# Orange_Board.net
KiCad netlist of a schematic drawn in EAGLE
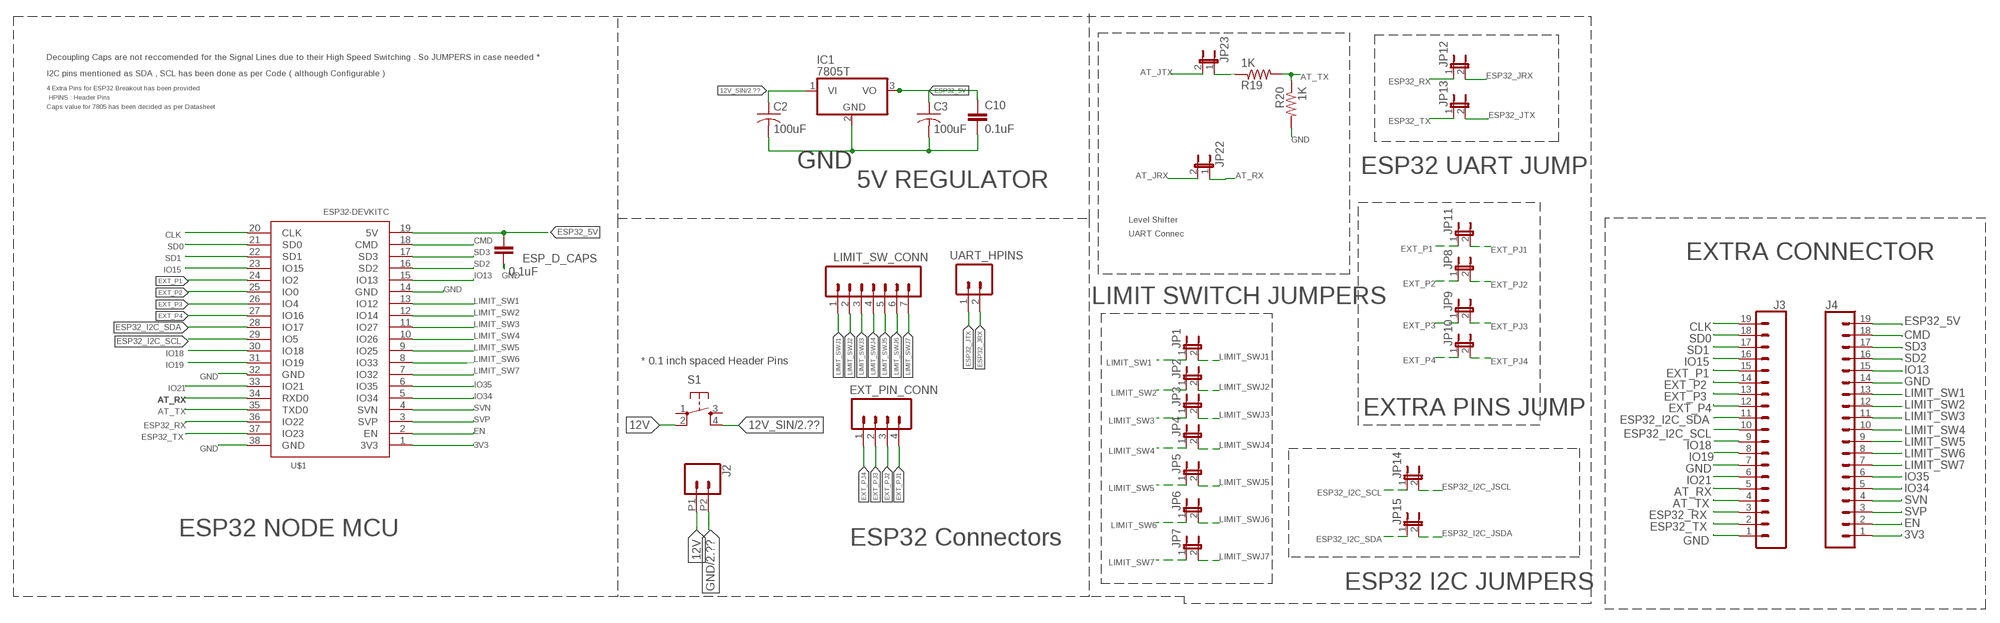
[diagram p0: schematic, sheet 1]
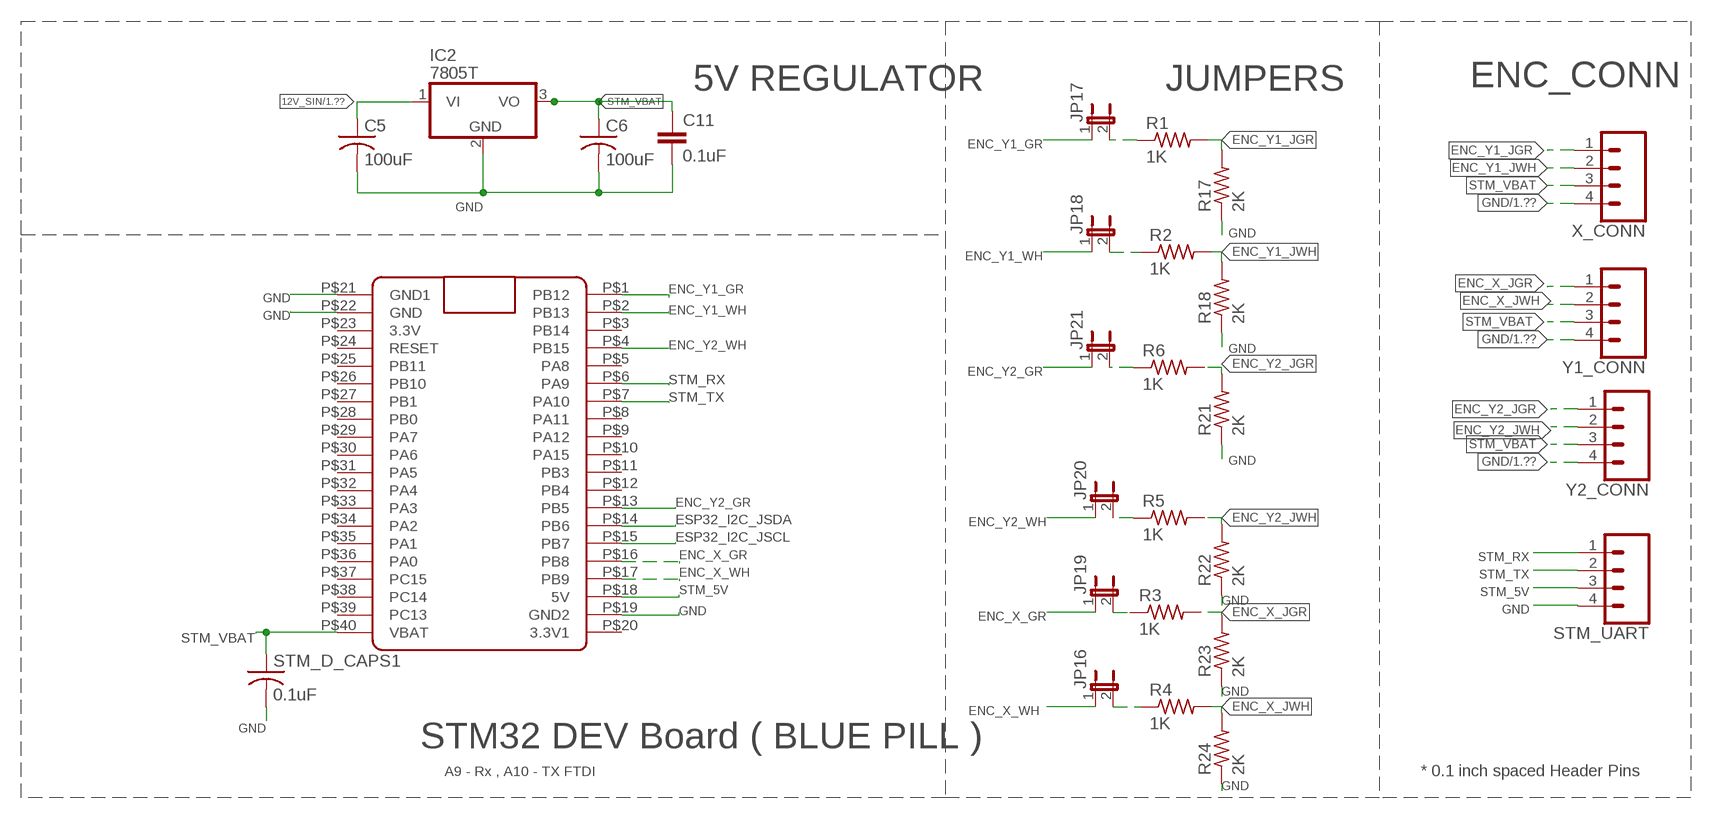
[diagram p1: schematic, sheet 2]
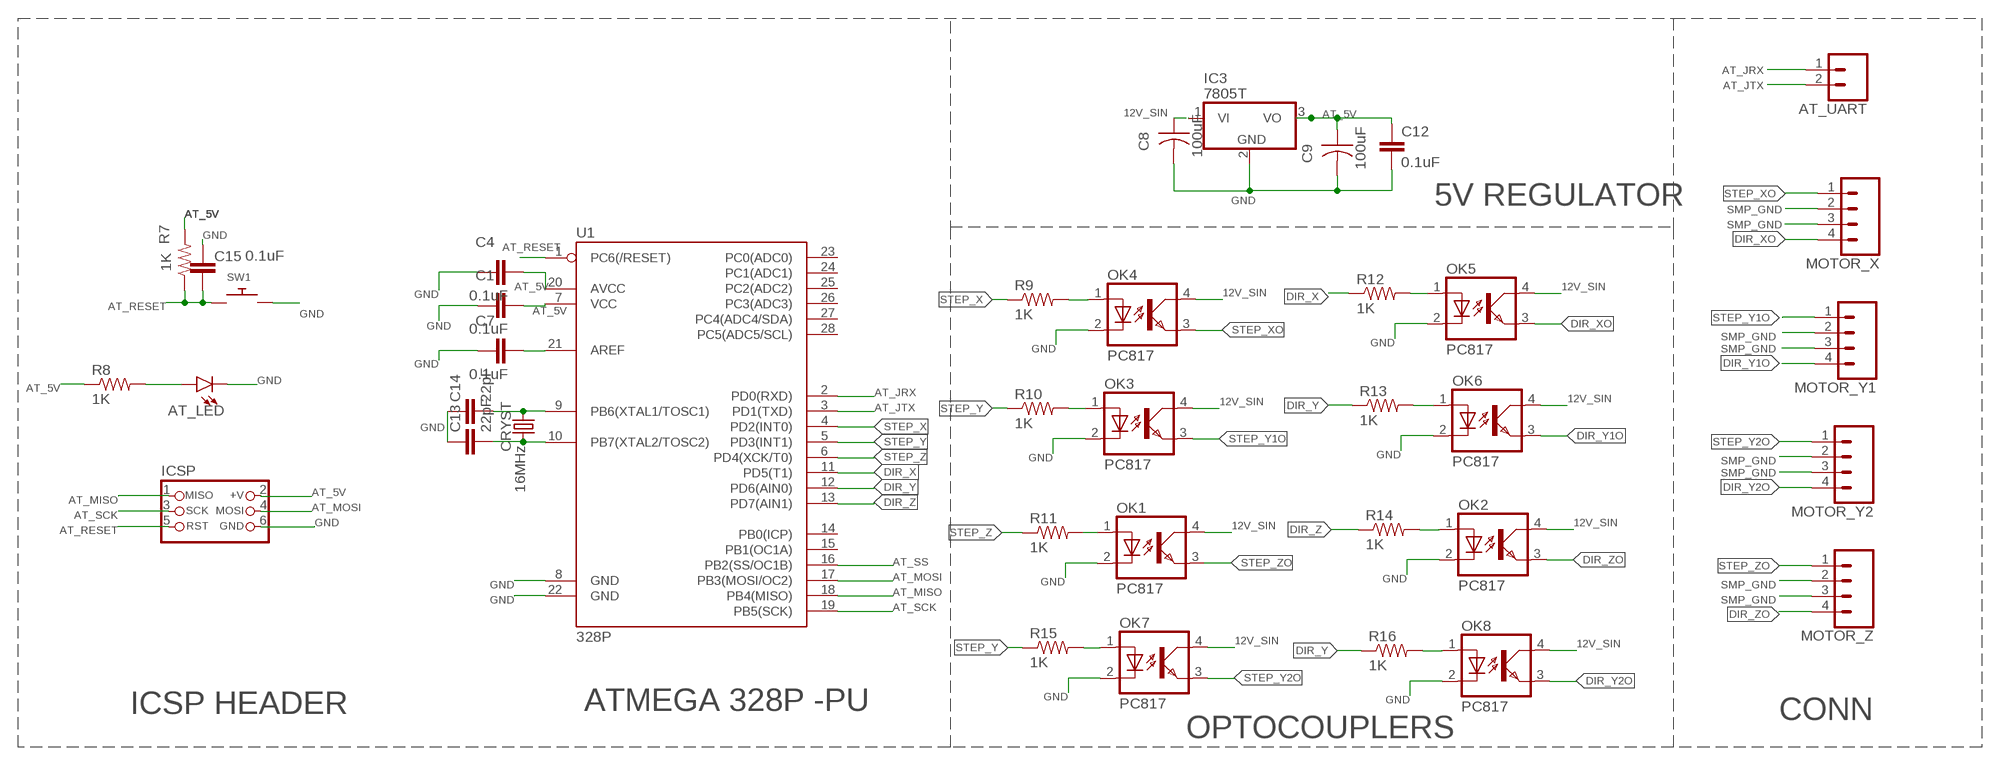
[diagram p2: schematic, sheet 3]

(export (version "E")
  (design (tool "Eeschema 10.0.6"))
  (components
    (comp (ref "C5")
      (value "100uF")
      (footprint "eagle-import:C025-024X044")
      (libsource (lib "eagle-import") (part "C-US025-024X044"))
    )
    (comp (ref "C6")
      (value "100uF")
      (footprint "eagle-import:C025-024X044")
      (libsource (lib "eagle-import") (part "C-US025-024X044"))
    )
    (comp (ref "C11")
      (value "0.1uF")
      (footprint "eagle-import:CAP-PTH-SMALL-KIT")
      (libsource (lib "eagle-import") (part "0.1UF-KIT-EZ-50V-20%"))
    )
    (comp (ref "IC2")
      (value "7805T")
      (footprint "eagle-import:TO220H")
      (libsource (lib "eagle-import") (part "78T05"))
    )
    (comp (ref "JP16")
      (value "JUMPER-2PTH")
      (footprint "eagle-import:1X02")
      (libsource (lib "eagle-import") (part "JUMPER-2PTH"))
    )
    (comp (ref "JP17")
      (value "JUMPER-2PTH")
      (footprint "eagle-import:1X02")
      (libsource (lib "eagle-import") (part "JUMPER-2PTH"))
    )
    (comp (ref "JP18")
      (value "JUMPER-2PTH")
      (footprint "eagle-import:1X02")
      (libsource (lib "eagle-import") (part "JUMPER-2PTH"))
    )
    (comp (ref "JP19")
      (value "JUMPER-2PTH")
      (footprint "eagle-import:1X02")
      (libsource (lib "eagle-import") (part "JUMPER-2PTH"))
    )
    (comp (ref "JP20")
      (value "JUMPER-2PTH")
      (footprint "eagle-import:1X02")
      (libsource (lib "eagle-import") (part "JUMPER-2PTH"))
    )
    (comp (ref "JP21")
      (value "JUMPER-2PTH")
      (footprint "eagle-import:1X02")
      (libsource (lib "eagle-import") (part "JUMPER-2PTH"))
    )
    (comp (ref "R1")
      (value "1K")
      (footprint "eagle-import:0204_5")
      (libsource (lib "eagle-import") (part "R-US_0204/5"))
    )
    (comp (ref "R2")
      (value "1K")
      (footprint "eagle-import:0204_5")
      (libsource (lib "eagle-import") (part "R-US_0204/5"))
    )
    (comp (ref "R3")
      (value "1K")
      (footprint "eagle-import:0204_5")
      (libsource (lib "eagle-import") (part "R-US_0204/5"))
    )
    (comp (ref "R4")
      (value "1K")
      (footprint "eagle-import:0204_5")
      (libsource (lib "eagle-import") (part "R-US_0204/5"))
    )
    (comp (ref "R5")
      (value "1K")
      (footprint "eagle-import:0204_5")
      (libsource (lib "eagle-import") (part "R-US_0204/5"))
    )
    (comp (ref "R6")
      (value "1K")
      (footprint "eagle-import:0204_5")
      (libsource (lib "eagle-import") (part "R-US_0204/5"))
    )
    (comp (ref "R17")
      (value "2K")
      (footprint "eagle-import:0204_5")
      (libsource (lib "eagle-import") (part "R-US_0204/5"))
    )
    (comp (ref "R18")
      (value "2K")
      (footprint "eagle-import:0204_5")
      (libsource (lib "eagle-import") (part "R-US_0204/5"))
    )
    (comp (ref "R21")
      (value "2K")
      (footprint "eagle-import:0204_5")
      (libsource (lib "eagle-import") (part "R-US_0204/5"))
    )
    (comp (ref "R22")
      (value "2K")
      (footprint "eagle-import:0204_5")
      (libsource (lib "eagle-import") (part "R-US_0204/5"))
    )
    (comp (ref "R23")
      (value "2K")
      (footprint "eagle-import:0204_5")
      (libsource (lib "eagle-import") (part "R-US_0204/5"))
    )
    (comp (ref "R24")
      (value "2K")
      (footprint "eagle-import:0204_5")
      (libsource (lib "eagle-import") (part "R-US_0204/5"))
    )
    (comp (ref "STM_D_CAPS1")
      (value "0.1uF")
      (footprint "eagle-import:C025-024X044")
      (libsource (lib "eagle-import") (part "C-US025-024X044"))
    )
    (comp (ref "STM_UART")
      (value "CONN_04")
      (footprint "eagle-import:1X04")
      (libsource (lib "eagle-import") (part "CONN_04"))
    )
    (comp (ref "U$2")
      (value "BLUE_PILLADVANCED")
      (footprint "eagle-import:BLUE_PILL_ADV")
      (libsource (lib "eagle-import") (part "BLUE_PILLADVANCED"))
    )
    (comp (ref "X_CONN")
      (value "CONN_04")
      (footprint "eagle-import:1X04")
      (libsource (lib "eagle-import") (part "CONN_04"))
    )
    (comp (ref "Y1_CONN")
      (value "CONN_04")
      (footprint "eagle-import:1X04")
      (libsource (lib "eagle-import") (part "CONN_04"))
    )
    (comp (ref "Y2_CONN")
      (value "CONN_04")
      (footprint "eagle-import:1X04")
      (libsource (lib "eagle-import") (part "CONN_04"))
    )
    (comp (ref "AT_LED")
      (value "LED-3MM-NO_SILK")
      (footprint "eagle-import:LED_3MM-NS")
      (libsource (lib "eagle-import") (part "LED-3MM-NO_SILK"))
    )
    (comp (ref "AT_UART")
      (value "CONN_02")
      (footprint "eagle-import:1X02")
      (libsource (lib "eagle-import") (part "CONN_02"))
    )
    (comp (ref "C1")
      (value "0.1uF")
      (footprint "eagle-import:CAP-PTH-SMALL-KIT")
      (libsource (lib "eagle-import") (part "0.1UF-KIT-EZ-50V-20%"))
    )
    (comp (ref "C4")
      (value "0.1uF")
      (footprint "eagle-import:CAP-PTH-SMALL-KIT")
      (libsource (lib "eagle-import") (part "0.1UF-KIT-EZ-50V-20%"))
    )
    (comp (ref "C7")
      (value "0.1uF")
      (footprint "eagle-import:CAP-PTH-SMALL-KIT")
      (libsource (lib "eagle-import") (part "0.1UF-KIT-EZ-50V-20%"))
    )
    (comp (ref "C8")
      (value "100uF")
      (footprint "eagle-import:C025-024X044")
      (libsource (lib "eagle-import") (part "C-US025-024X044"))
    )
    (comp (ref "C9")
      (value "100uF")
      (footprint "eagle-import:C025-024X044")
      (libsource (lib "eagle-import") (part "C-US025-024X044"))
    )
    (comp (ref "C12")
      (value "0.1uF")
      (footprint "eagle-import:CAP-PTH-SMALL-KIT")
      (libsource (lib "eagle-import") (part "0.1UF-KIT-EZ-50V-20%"))
    )
    (comp (ref "C13")
      (value "22pF")
      (footprint "eagle-import:CAP-PTH-2.54")
      (libsource (lib "eagle-import") (part "22PF-PTH-2.54MM-200V-5%"))
    )
    (comp (ref "C14")
      (value "22pF")
      (footprint "eagle-import:CAP-PTH-2.54")
      (libsource (lib "eagle-import") (part "22PF-PTH-2.54MM-200V-5%"))
    )
    (comp (ref "C15")
      (value "0.1uF")
      (footprint "eagle-import:CAP-PTH-SMALL-KIT")
      (libsource (lib "eagle-import") (part "0.1UF-KIT-EZ-50V-20%"))
    )
    (comp (ref "CRYST")
      (value "16MHz")
      (footprint "eagle-import:HC49US")
      (libsource (lib "eagle-import") (part "CRYSTAL-16MHZPTH-HC49US"))
    )
    (comp (ref "IC3")
      (value "7805T")
      (footprint "eagle-import:TO220H")
      (libsource (lib "eagle-import") (part "78T05"))
    )
    (comp (ref "ICSP")
      (value "CON_HEADER_PRG_AVR_ICSP-PTH")
      (footprint "eagle-import:HEADER_PRG_2X03")
      (libsource (lib "eagle-import") (part "CON_HEADER_PRG_AVR_ICSP-PTH"))
    )
    (comp (ref "MOTOR_X")
      (value "CONN_04")
      (footprint "eagle-import:1X04")
      (libsource (lib "eagle-import") (part "CONN_04"))
    )
    (comp (ref "MOTOR_Y1")
      (value "CONN_04")
      (footprint "eagle-import:1X04")
      (libsource (lib "eagle-import") (part "CONN_04"))
    )
    (comp (ref "MOTOR_Y2")
      (value "CONN_04")
      (footprint "eagle-import:1X04")
      (libsource (lib "eagle-import") (part "CONN_04"))
    )
    (comp (ref "MOTOR_Z")
      (value "CONN_04")
      (footprint "eagle-import:1X04")
      (libsource (lib "eagle-import") (part "CONN_04"))
    )
    (comp (ref "OK1")
      (value "PC817")
      (footprint "eagle-import:DIL04")
      (fields (field (name "MPN") "PC817X4J000F"))
      (libsource (lib "eagle-import") (part "PC817"))
    )
    (comp (ref "OK2")
      (value "PC817")
      (footprint "eagle-import:DIL04")
      (fields (field (name "MPN") "PC817X4J000F"))
      (libsource (lib "eagle-import") (part "PC817"))
    )
    (comp (ref "OK3")
      (value "PC817")
      (footprint "eagle-import:DIL04")
      (fields (field (name "MPN") "PC817X4J000F"))
      (libsource (lib "eagle-import") (part "PC817"))
    )
    (comp (ref "OK4")
      (value "PC817")
      (footprint "eagle-import:DIL04")
      (fields (field (name "MPN") "PC817X4J000F"))
      (libsource (lib "eagle-import") (part "PC817"))
    )
    (comp (ref "OK5")
      (value "PC817")
      (footprint "eagle-import:DIL04")
      (fields (field (name "MPN") "PC817X4J000F"))
      (libsource (lib "eagle-import") (part "PC817"))
    )
    (comp (ref "OK6")
      (value "PC817")
      (footprint "eagle-import:DIL04")
      (fields (field (name "MPN") "PC817X4J000F"))
      (libsource (lib "eagle-import") (part "PC817"))
    )
    (comp (ref "OK7")
      (value "PC817")
      (footprint "eagle-import:DIL04")
      (fields (field (name "MPN") "PC817X4J000F"))
      (libsource (lib "eagle-import") (part "PC817"))
    )
    (comp (ref "OK8")
      (value "PC817")
      (footprint "eagle-import:DIL04")
      (fields (field (name "MPN") "PC817X4J000F"))
      (libsource (lib "eagle-import") (part "PC817"))
    )
    (comp (ref "R7")
      (value "1K")
      (footprint "eagle-import:0204_5")
      (libsource (lib "eagle-import") (part "R-US_0204/5"))
    )
    (comp (ref "R8")
      (value "1K")
      (footprint "eagle-import:0204_5")
      (libsource (lib "eagle-import") (part "R-US_0204/5"))
    )
    (comp (ref "R9")
      (value "1K")
      (footprint "eagle-import:0204_5")
      (libsource (lib "eagle-import") (part "R-US_0204/5"))
    )
    (comp (ref "R10")
      (value "1K")
      (footprint "eagle-import:0204_5")
      (libsource (lib "eagle-import") (part "R-US_0204/5"))
    )
    (comp (ref "R11")
      (value "1K")
      (footprint "eagle-import:0204_5")
      (libsource (lib "eagle-import") (part "R-US_0204/5"))
    )
    (comp (ref "R12")
      (value "1K")
      (footprint "eagle-import:0204_5")
      (libsource (lib "eagle-import") (part "R-US_0204/5"))
    )
    (comp (ref "R13")
      (value "1K")
      (footprint "eagle-import:0204_5")
      (libsource (lib "eagle-import") (part "R-US_0204/5"))
    )
    (comp (ref "R14")
      (value "1K")
      (footprint "eagle-import:0204_5")
      (libsource (lib "eagle-import") (part "R-US_0204/5"))
    )
    (comp (ref "R15")
      (value "1K")
      (footprint "eagle-import:0204_5")
      (libsource (lib "eagle-import") (part "R-US_0204/5"))
    )
    (comp (ref "R16")
      (value "1K")
      (footprint "eagle-import:0204_5")
      (libsource (lib "eagle-import") (part "R-US_0204/5"))
    )
    (comp (ref "SW1")
      (value "SWITCH_PUSHBUTTONEVQ-PE")
      (footprint "eagle-import:TACT_PANA-EVQ")
      (libsource (lib "eagle-import") (part "SWITCH_PUSHBUTTONEVQ-PE"))
    )
    (comp (ref "U1")
      (value "328P")
      (footprint "eagle-import:DIP28")
      (libsource (lib "eagle-import") (part "ATMEGA328P_PDIP"))
    )
    (comp (ref "C2")
      (value "100uF")
      (footprint "eagle-import:C025-024X044")
      (libsource (lib "eagle-import") (part "C-US025-024X044"))
    )
    (comp (ref "C3")
      (value "100uF")
      (footprint "eagle-import:C025-024X044")
      (libsource (lib "eagle-import") (part "C-US025-024X044"))
    )
    (comp (ref "C10")
      (value "0.1uF")
      (footprint "eagle-import:CAP-PTH-SMALL-KIT")
      (libsource (lib "eagle-import") (part "0.1UF-KIT-EZ-50V-20%"))
    )
    (comp (ref "ESP_D_CAPS")
      (value "0.1uF")
      (footprint "eagle-import:CAP-PTH-SMALL-KIT")
      (libsource (lib "eagle-import") (part "0.1UF-KIT-EZ-50V-20%"))
    )
    (comp (ref "EXT_PIN_CONN")
      (value "CONN_04")
      (footprint "eagle-import:1X04")
      (libsource (lib "eagle-import") (part "CONN_04"))
    )
    (comp (ref "IC1")
      (value "7805T")
      (footprint "eagle-import:TO220H")
      (libsource (lib "eagle-import") (part "78T05"))
    )
    (comp (ref "J2")
      (value "CONN_022.54MM_SCREWTERM")
      (footprint "eagle-import:1X02_2.54_SCREWTERM")
      (libsource (lib "eagle-import") (part "CONN_022.54MM_SCREWTERM"))
    )
    (comp (ref "J3")
      (value "CONN_19")
      (footprint "eagle-import:1X19")
      (libsource (lib "eagle-import") (part "CONN_19"))
    )
    (comp (ref "J4")
      (value "CONN_19")
      (footprint "eagle-import:1X19")
      (libsource (lib "eagle-import") (part "CONN_19"))
    )
    (comp (ref "JP1")
      (value "JUMPER-2PTH")
      (footprint "eagle-import:1X02")
      (libsource (lib "eagle-import") (part "JUMPER-2PTH"))
    )
    (comp (ref "JP2")
      (value "JUMPER-2PTH")
      (footprint "eagle-import:1X02")
      (libsource (lib "eagle-import") (part "JUMPER-2PTH"))
    )
    (comp (ref "JP3")
      (value "JUMPER-2PTH")
      (footprint "eagle-import:1X02")
      (libsource (lib "eagle-import") (part "JUMPER-2PTH"))
    )
    (comp (ref "JP4")
      (value "JUMPER-2PTH")
      (footprint "eagle-import:1X02")
      (libsource (lib "eagle-import") (part "JUMPER-2PTH"))
    )
    (comp (ref "JP5")
      (value "JUMPER-2PTH")
      (footprint "eagle-import:1X02")
      (libsource (lib "eagle-import") (part "JUMPER-2PTH"))
    )
    (comp (ref "JP6")
      (value "JUMPER-2PTH")
      (footprint "eagle-import:1X02")
      (libsource (lib "eagle-import") (part "JUMPER-2PTH"))
    )
    (comp (ref "JP7")
      (value "JUMPER-2PTH")
      (footprint "eagle-import:1X02")
      (libsource (lib "eagle-import") (part "JUMPER-2PTH"))
    )
    (comp (ref "JP8")
      (value "JUMPER-2PTH")
      (footprint "eagle-import:1X02")
      (libsource (lib "eagle-import") (part "JUMPER-2PTH"))
    )
    (comp (ref "JP9")
      (value "JUMPER-2PTH")
      (footprint "eagle-import:1X02")
      (libsource (lib "eagle-import") (part "JUMPER-2PTH"))
    )
    (comp (ref "JP10")
      (value "JUMPER-2PTH")
      (footprint "eagle-import:1X02")
      (libsource (lib "eagle-import") (part "JUMPER-2PTH"))
    )
    (comp (ref "JP11")
      (value "JUMPER-2PTH")
      (footprint "eagle-import:1X02")
      (libsource (lib "eagle-import") (part "JUMPER-2PTH"))
    )
    (comp (ref "JP12")
      (value "JUMPER-2PTH")
      (footprint "eagle-import:1X02")
      (libsource (lib "eagle-import") (part "JUMPER-2PTH"))
    )
    (comp (ref "JP13")
      (value "JUMPER-2PTH")
      (footprint "eagle-import:1X02")
      (libsource (lib "eagle-import") (part "JUMPER-2PTH"))
    )
    (comp (ref "JP14")
      (value "JUMPER-2PTH")
      (footprint "eagle-import:1X02")
      (libsource (lib "eagle-import") (part "JUMPER-2PTH"))
    )
    (comp (ref "JP15")
      (value "JUMPER-2PTH")
      (footprint "eagle-import:1X02")
      (libsource (lib "eagle-import") (part "JUMPER-2PTH"))
    )
    (comp (ref "JP22")
      (value "JUMPER-2PTH")
      (footprint "eagle-import:1X02")
      (libsource (lib "eagle-import") (part "JUMPER-2PTH"))
    )
    (comp (ref "JP23")
      (value "JUMPER-2PTH")
      (footprint "eagle-import:1X02")
      (libsource (lib "eagle-import") (part "JUMPER-2PTH"))
    )
    (comp (ref "LIMIT_SW_CONN")
      (value "CONN_07")
      (footprint "eagle-import:1X07")
      (libsource (lib "eagle-import") (part "CONN_07"))
    )
    (comp (ref "R19")
      (value "1K")
      (footprint "eagle-import:0204_5")
      (libsource (lib "eagle-import") (part "R-US_0204/5"))
    )
    (comp (ref "R20")
      (value "1K")
      (footprint "eagle-import:0204_5")
      (libsource (lib "eagle-import") (part "R-US_0204/5"))
    )
    (comp (ref "S1")
      (value "TAC_SWITCHPTH")
      (footprint "eagle-import:TACTILE-PTH")
      (libsource (lib "eagle-import") (part "TAC_SWITCHPTH"))
    )
    (comp (ref "U$1")
      (value "ESP32DEVKITC")
      (footprint "eagle-import:ESP32-DEVKITC")
      (libsource (lib "eagle-import") (part "ESP32DEVKITC"))
    )
    (comp (ref "UART_HPINS")
      (value "CONN_02")
      (footprint "eagle-import:1X02")
      (libsource (lib "eagle-import") (part "CONN_02"))
    )
  )
  (nets
    (net (code "1") (name "3V3") (class "Default")
      (node (ref "J4") (pin "1") (pinfunction "1_1") (pintype "passive"))
      (node (ref "U$1") (pin "1") (pinfunction "3V3_1") (pintype "bidirectional"))
    )
    (net (code "2") (name "12V") (class "Default")
      (node (ref "J2") (pin "P1") (pinfunction "1_P1") (pintype "passive"))
      (node (ref "S1") (pin "2") (pinfunction "2_2") (pintype "passive"))
    )
    (net (code "3") (name "12V_SIN") (class "Default")
      (node (ref "C2") (pin "1") (pinfunction "1_1") (pintype "passive"))
      (node (ref "C5") (pin "1") (pinfunction "1_1") (pintype "passive"))
      (node (ref "C8") (pin "1") (pinfunction "1_1") (pintype "passive"))
      (node (ref "IC1") (pin "1") (pinfunction "VI_1") (pintype "input"))
      (node (ref "IC2") (pin "1") (pinfunction "VI_1") (pintype "input"))
      (node (ref "IC3") (pin "1") (pinfunction "VI_1") (pintype "input"))
      (node (ref "OK1") (pin "4") (pinfunction "COL_4") (pintype "passive"))
      (node (ref "OK2") (pin "4") (pinfunction "COL_4") (pintype "passive"))
      (node (ref "OK3") (pin "4") (pinfunction "COL_4") (pintype "passive"))
      (node (ref "OK4") (pin "4") (pinfunction "COL_4") (pintype "passive"))
      (node (ref "OK5") (pin "4") (pinfunction "COL_4") (pintype "passive"))
      (node (ref "OK6") (pin "4") (pinfunction "COL_4") (pintype "passive"))
      (node (ref "OK7") (pin "4") (pinfunction "COL_4") (pintype "passive"))
      (node (ref "OK8") (pin "4") (pinfunction "COL_4") (pintype "passive"))
      (node (ref "S1") (pin "4") (pinfunction "4_4") (pintype "passive"))
    )
    (net (code "4") (name "AT_5V") (class "Default")
      (node (ref "C1") (pin "1") (pinfunction "1_1") (pintype "passive"))
      (node (ref "C12") (pin "1") (pinfunction "1_1") (pintype "passive"))
      (node (ref "C4") (pin "1") (pinfunction "1_1") (pintype "passive"))
      (node (ref "C9") (pin "1") (pinfunction "1_1") (pintype "passive"))
      (node (ref "IC3") (pin "3") (pinfunction "VO_3") (pintype "passive"))
      (node (ref "ICSP") (pin "2") (pinfunction "+V_2") (pintype "passive"))
      (node (ref "R7") (pin "2") (pinfunction "2_2") (pintype "passive"))
      (node (ref "R8") (pin "1") (pinfunction "1_1") (pintype "passive"))
      (node (ref "U1") (pin "20") (pinfunction "AVCC_20") (pintype "bidirectional"))
      (node (ref "U1") (pin "7") (pinfunction "VCC_7") (pintype "bidirectional"))
    )
    (net (code "5") (name "AT_JRX") (class "Default")
      (node (ref "AT_UART") (pin "1") (pinfunction "1_1") (pintype "passive"))
      (node (ref "JP22") (pin "2") (pinfunction "2_2") (pintype "passive"))
      (node (ref "U1") (pin "2") (pinfunction "PD0(RXD)_2") (pintype "bidirectional"))
    )
    (net (code "6") (name "AT_JTX") (class "Default")
      (node (ref "AT_UART") (pin "2") (pinfunction "2_2") (pintype "passive"))
      (node (ref "JP23") (pin "2") (pinfunction "2_2") (pintype "passive"))
      (node (ref "U1") (pin "3") (pinfunction "PD1(TXD)_3") (pintype "bidirectional"))
    )
    (net (code "7") (name "AT_MISO") (class "Default")
      (node (ref "ICSP") (pin "1") (pinfunction "MISO_1") (pintype "passive"))
      (node (ref "U1") (pin "18") (pinfunction "PB4(MISO)_18") (pintype "bidirectional"))
    )
    (net (code "8") (name "AT_MOSI") (class "Default")
      (node (ref "ICSP") (pin "4") (pinfunction "MOSI_4") (pintype "passive"))
      (node (ref "U1") (pin "17") (pinfunction "PB3(MOSI/OC2)_17") (pintype "bidirectional"))
    )
    (net (code "9") (name "AT_RESET") (class "Default")
      (node (ref "C15") (pin "1") (pinfunction "1_1") (pintype "passive"))
      (node (ref "ICSP") (pin "5") (pinfunction "RST_5") (pintype "passive"))
      (node (ref "R7") (pin "1") (pinfunction "1_1") (pintype "passive"))
      (node (ref "SW1") (pin "P$1") (pinfunction "P$1_P$1") (pintype "passive"))
      (node (ref "U1") (pin "1") (pinfunction "PC6(/RESET)_1") (pintype "bidirectional"))
    )
    (net (code "10") (name "AT_RX") (class "Default")
      (node (ref "J3") (pin "5") (pinfunction "5_5") (pintype "passive"))
      (node (ref "JP22") (pin "1") (pinfunction "1_1") (pintype "passive"))
      (node (ref "U$1") (pin "34") (pinfunction "RXD0_34") (pintype "bidirectional"))
    )
    (net (code "11") (name "AT_SCK") (class "Default")
      (node (ref "ICSP") (pin "3") (pinfunction "SCK_3") (pintype "passive"))
      (node (ref "U1") (pin "19") (pinfunction "PB5(SCK)_19") (pintype "bidirectional"))
    )
    (net (code "12") (name "AT_SS") (class "Default")
      (node (ref "U1") (pin "16") (pinfunction "PB2(SS/OC1B)_16") (pintype "bidirectional"))
    )
    (net (code "13") (name "AT_TX") (class "Default")
      (node (ref "J3") (pin "4") (pinfunction "4_4") (pintype "passive"))
      (node (ref "R19") (pin "2") (pinfunction "2_2") (pintype "passive"))
      (node (ref "R20") (pin "1") (pinfunction "1_1") (pintype "passive"))
      (node (ref "U$1") (pin "35") (pinfunction "TXD0_35") (pintype "bidirectional"))
    )
    (net (code "14") (name "CLK") (class "Default")
      (node (ref "J3") (pin "19") (pinfunction "19_19") (pintype "passive"))
      (node (ref "U$1") (pin "20") (pinfunction "CLK_20") (pintype "bidirectional"))
    )
    (net (code "15") (name "CMD") (class "Default")
      (node (ref "J4") (pin "18") (pinfunction "18_18") (pintype "passive"))
      (node (ref "U$1") (pin "18") (pinfunction "CMD_18") (pintype "bidirectional"))
    )
    (net (code "16") (name "DIR_X") (class "Default")
      (node (ref "R12") (pin "1") (pinfunction "1_1") (pintype "passive"))
      (node (ref "U1") (pin "11") (pinfunction "PD5(T1)_11") (pintype "bidirectional"))
    )
    (net (code "17") (name "DIR_XO") (class "Default")
      (node (ref "MOTOR_X") (pin "4") (pinfunction "4_4") (pintype "passive"))
      (node (ref "OK5") (pin "3") (pinfunction "EMIT_3") (pintype "passive"))
    )
    (net (code "18") (name "DIR_Y") (class "Default")
      (node (ref "R13") (pin "1") (pinfunction "1_1") (pintype "passive"))
      (node (ref "R16") (pin "1") (pinfunction "1_1") (pintype "passive"))
      (node (ref "U1") (pin "12") (pinfunction "PD6(AIN0)_12") (pintype "bidirectional"))
    )
    (net (code "19") (name "DIR_Y1O") (class "Default")
      (node (ref "MOTOR_Y1") (pin "4") (pinfunction "4_4") (pintype "passive"))
      (node (ref "OK6") (pin "3") (pinfunction "EMIT_3") (pintype "passive"))
    )
    (net (code "20") (name "DIR_Y2O") (class "Default")
      (node (ref "MOTOR_Y2") (pin "4") (pinfunction "4_4") (pintype "passive"))
      (node (ref "OK8") (pin "3") (pinfunction "EMIT_3") (pintype "passive"))
    )
    (net (code "21") (name "DIR_Z") (class "Default")
      (node (ref "R14") (pin "1") (pinfunction "1_1") (pintype "passive"))
      (node (ref "U1") (pin "13") (pinfunction "PD7(AIN1)_13") (pintype "bidirectional"))
    )
    (net (code "22") (name "DIR_ZO") (class "Default")
      (node (ref "MOTOR_Z") (pin "4") (pinfunction "4_4") (pintype "passive"))
      (node (ref "OK2") (pin "3") (pinfunction "EMIT_3") (pintype "passive"))
    )
    (net (code "23") (name "EN") (class "Default")
      (node (ref "J4") (pin "2") (pinfunction "2_2") (pintype "passive"))
      (node (ref "U$1") (pin "2") (pinfunction "EN_2") (pintype "bidirectional"))
    )
    (net (code "24") (name "ENC_X_GR") (class "Default")
      (node (ref "JP19") (pin "1") (pinfunction "1_1") (pintype "passive"))
      (node (ref "U$2") (pin "P$16") (pinfunction "PB8_P$16") (pintype "bidirectional"))
    )
    (net (code "25") (name "ENC_X_JGR") (class "Default")
      (node (ref "R23") (pin "2") (pinfunction "2_2") (pintype "passive"))
      (node (ref "R3") (pin "2") (pinfunction "2_2") (pintype "passive"))
      (node (ref "Y1_CONN") (pin "1") (pinfunction "1_1") (pintype "passive"))
    )
    (net (code "26") (name "ENC_X_JWH") (class "Default")
      (node (ref "R24") (pin "2") (pinfunction "2_2") (pintype "passive"))
      (node (ref "R4") (pin "2") (pinfunction "2_2") (pintype "passive"))
      (node (ref "Y1_CONN") (pin "2") (pinfunction "2_2") (pintype "passive"))
    )
    (net (code "27") (name "ENC_X_WH") (class "Default")
      (node (ref "JP16") (pin "1") (pinfunction "1_1") (pintype "passive"))
      (node (ref "U$2") (pin "P$17") (pinfunction "PB9_P$17") (pintype "bidirectional"))
    )
    (net (code "28") (name "ENC_Y1_GR") (class "Default")
      (node (ref "JP17") (pin "1") (pinfunction "1_1") (pintype "passive"))
      (node (ref "U$2") (pin "P$1") (pinfunction "PB12_P$1") (pintype "bidirectional"))
    )
    (net (code "29") (name "ENC_Y1_JGR") (class "Default")
      (node (ref "R1") (pin "2") (pinfunction "2_2") (pintype "passive"))
      (node (ref "R17") (pin "2") (pinfunction "2_2") (pintype "passive"))
      (node (ref "X_CONN") (pin "1") (pinfunction "1_1") (pintype "passive"))
    )
    (net (code "30") (name "ENC_Y1_JWH") (class "Default")
      (node (ref "R18") (pin "2") (pinfunction "2_2") (pintype "passive"))
      (node (ref "R2") (pin "2") (pinfunction "2_2") (pintype "passive"))
      (node (ref "X_CONN") (pin "2") (pinfunction "2_2") (pintype "passive"))
    )
    (net (code "31") (name "ENC_Y1_WH") (class "Default")
      (node (ref "JP18") (pin "1") (pinfunction "1_1") (pintype "passive"))
      (node (ref "U$2") (pin "P$2") (pinfunction "PB13_P$2") (pintype "bidirectional"))
    )
    (net (code "32") (name "ENC_Y2_GR") (class "Default")
      (node (ref "JP21") (pin "1") (pinfunction "1_1") (pintype "passive"))
      (node (ref "U$2") (pin "P$13") (pinfunction "PB5_P$13") (pintype "bidirectional"))
    )
    (net (code "33") (name "ENC_Y2_JGR") (class "Default")
      (node (ref "R21") (pin "2") (pinfunction "2_2") (pintype "passive"))
      (node (ref "R6") (pin "2") (pinfunction "2_2") (pintype "passive"))
      (node (ref "Y2_CONN") (pin "1") (pinfunction "1_1") (pintype "passive"))
    )
    (net (code "34") (name "ENC_Y2_JWH") (class "Default")
      (node (ref "R22") (pin "2") (pinfunction "2_2") (pintype "passive"))
      (node (ref "R5") (pin "2") (pinfunction "2_2") (pintype "passive"))
      (node (ref "Y2_CONN") (pin "2") (pinfunction "2_2") (pintype "passive"))
    )
    (net (code "35") (name "ENC_Y2_WH") (class "Default")
      (node (ref "JP20") (pin "1") (pinfunction "1_1") (pintype "passive"))
      (node (ref "U$2") (pin "P$4") (pinfunction "PB15_P$4") (pintype "bidirectional"))
    )
    (net (code "36") (name "ESP32_5V") (class "Default")
      (node (ref "C10") (pin "1") (pinfunction "1_1") (pintype "passive"))
      (node (ref "C3") (pin "1") (pinfunction "1_1") (pintype "passive"))
      (node (ref "ESP_D_CAPS") (pin "1") (pinfunction "1_1") (pintype "passive"))
      (node (ref "IC1") (pin "3") (pinfunction "VO_3") (pintype "passive"))
      (node (ref "J4") (pin "19") (pinfunction "19_19") (pintype "passive"))
      (node (ref "U$1") (pin "19") (pinfunction "5V_19") (pintype "bidirectional"))
    )
    (net (code "37") (name "ESP32_I2C_JSCL") (class "Default")
      (node (ref "JP14") (pin "2") (pinfunction "2_2") (pintype "passive"))
      (node (ref "U$2") (pin "P$15") (pinfunction "PB7_P$15") (pintype "bidirectional"))
    )
    (net (code "38") (name "ESP32_I2C_JSDA") (class "Default")
      (node (ref "JP15") (pin "2") (pinfunction "2_2") (pintype "passive"))
      (node (ref "U$2") (pin "P$14") (pinfunction "PB6_P$14") (pintype "bidirectional"))
    )
    (net (code "39") (name "ESP32_I2C_SCL") (class "Default")
      (node (ref "J3") (pin "10") (pinfunction "10_10") (pintype "passive"))
      (node (ref "JP14") (pin "1") (pinfunction "1_1") (pintype "passive"))
      (node (ref "U$1") (pin "29") (pinfunction "IO5_29") (pintype "bidirectional"))
    )
    (net (code "40") (name "ESP32_I2C_SDA") (class "Default")
      (node (ref "J3") (pin "11") (pinfunction "11_11") (pintype "passive"))
      (node (ref "JP15") (pin "1") (pinfunction "1_1") (pintype "passive"))
      (node (ref "U$1") (pin "28") (pinfunction "IO17_28") (pintype "bidirectional"))
    )
    (net (code "41") (name "ESP32_JRX") (class "Default")
      (node (ref "JP12") (pin "2") (pinfunction "2_2") (pintype "passive"))
      (node (ref "UART_HPINS") (pin "2") (pinfunction "2_2") (pintype "passive"))
    )
    (net (code "42") (name "ESP32_JTX") (class "Default")
      (node (ref "JP13") (pin "2") (pinfunction "2_2") (pintype "passive"))
      (node (ref "UART_HPINS") (pin "1") (pinfunction "1_1") (pintype "passive"))
    )
    (net (code "43") (name "ESP32_RX") (class "Default")
      (node (ref "J3") (pin "3") (pinfunction "3_3") (pintype "passive"))
      (node (ref "JP12") (pin "1") (pinfunction "1_1") (pintype "passive"))
      (node (ref "U$1") (pin "36") (pinfunction "IO22_36") (pintype "bidirectional"))
    )
    (net (code "44") (name "ESP32_TX") (class "Default")
      (node (ref "J3") (pin "2") (pinfunction "2_2") (pintype "passive"))
      (node (ref "JP13") (pin "1") (pinfunction "1_1") (pintype "passive"))
      (node (ref "U$1") (pin "37") (pinfunction "IO23_37") (pintype "bidirectional"))
    )
    (net (code "45") (name "EXT_P1") (class "Default")
      (node (ref "J3") (pin "15") (pinfunction "15_15") (pintype "passive"))
      (node (ref "JP11") (pin "1") (pinfunction "1_1") (pintype "passive"))
      (node (ref "U$1") (pin "24") (pinfunction "IO2_24") (pintype "bidirectional"))
    )
    (net (code "46") (name "EXT_P2") (class "Default")
      (node (ref "J3") (pin "14") (pinfunction "14_14") (pintype "passive"))
      (node (ref "JP8") (pin "1") (pinfunction "1_1") (pintype "passive"))
      (node (ref "U$1") (pin "25") (pinfunction "IO0_25") (pintype "bidirectional"))
    )
    (net (code "47") (name "EXT_P3") (class "Default")
      (node (ref "J3") (pin "13") (pinfunction "13_13") (pintype "passive"))
      (node (ref "JP9") (pin "1") (pinfunction "1_1") (pintype "passive"))
      (node (ref "U$1") (pin "26") (pinfunction "IO4_26") (pintype "bidirectional"))
    )
    (net (code "48") (name "EXT_P4") (class "Default")
      (node (ref "J3") (pin "12") (pinfunction "12_12") (pintype "passive"))
      (node (ref "JP10") (pin "1") (pinfunction "1_1") (pintype "passive"))
      (node (ref "U$1") (pin "27") (pinfunction "IO16_27") (pintype "bidirectional"))
    )
    (net (code "49") (name "EXT_PJ1") (class "Default")
      (node (ref "EXT_PIN_CONN") (pin "4") (pinfunction "4_4") (pintype "passive"))
      (node (ref "JP11") (pin "2") (pinfunction "2_2") (pintype "passive"))
    )
    (net (code "50") (name "EXT_PJ2") (class "Default")
      (node (ref "EXT_PIN_CONN") (pin "3") (pinfunction "3_3") (pintype "passive"))
      (node (ref "JP8") (pin "2") (pinfunction "2_2") (pintype "passive"))
    )
    (net (code "51") (name "EXT_PJ3") (class "Default")
      (node (ref "EXT_PIN_CONN") (pin "2") (pinfunction "2_2") (pintype "passive"))
      (node (ref "JP9") (pin "2") (pinfunction "2_2") (pintype "passive"))
    )
    (net (code "52") (name "EXT_PJ4") (class "Default")
      (node (ref "EXT_PIN_CONN") (pin "1") (pinfunction "1_1") (pintype "passive"))
      (node (ref "JP10") (pin "2") (pinfunction "2_2") (pintype "passive"))
    )
    (net (code "53") (name "GND") (class "Default")
      (node (ref "AT_LED") (pin "K") (pinfunction "C_K") (pintype "passive"))
      (node (ref "C1") (pin "2") (pinfunction "2_2") (pintype "passive"))
      (node (ref "C10") (pin "2") (pinfunction "2_2") (pintype "passive"))
      (node (ref "C11") (pin "2") (pinfunction "2_2") (pintype "passive"))
      (node (ref "C12") (pin "2") (pinfunction "2_2") (pintype "passive"))
      (node (ref "C13") (pin "1") (pinfunction "1_1") (pintype "passive"))
      (node (ref "C14") (pin "1") (pinfunction "1_1") (pintype "passive"))
      (node (ref "C15") (pin "2") (pinfunction "2_2") (pintype "passive"))
      (node (ref "C2") (pin "2") (pinfunction "2_2") (pintype "passive"))
      (node (ref "C3") (pin "2") (pinfunction "2_2") (pintype "passive"))
      (node (ref "C4") (pin "2") (pinfunction "2_2") (pintype "passive"))
      (node (ref "C5") (pin "2") (pinfunction "2_2") (pintype "passive"))
      (node (ref "C6") (pin "2") (pinfunction "2_2") (pintype "passive"))
      (node (ref "C7") (pin "2") (pinfunction "2_2") (pintype "passive"))
      (node (ref "C8") (pin "2") (pinfunction "2_2") (pintype "passive"))
      (node (ref "C9") (pin "2") (pinfunction "2_2") (pintype "passive"))
      (node (ref "ESP_D_CAPS") (pin "2") (pinfunction "2_2") (pintype "passive"))
      (node (ref "IC1") (pin "2") (pinfunction "GND_2") (pintype "passive"))
      (node (ref "IC2") (pin "2") (pinfunction "GND_2") (pintype "passive"))
      (node (ref "IC3") (pin "2") (pinfunction "GND_2") (pintype "passive"))
      (node (ref "ICSP") (pin "6") (pinfunction "GND_6") (pintype "passive"))
      (node (ref "J2") (pin "P2") (pinfunction "2_P2") (pintype "passive"))
      (node (ref "J3") (pin "1") (pinfunction "1_1") (pintype "passive"))
      (node (ref "J3") (pin "7") (pinfunction "7_7") (pintype "passive"))
      (node (ref "J4") (pin "14") (pinfunction "14_14") (pintype "passive"))
      (node (ref "OK1") (pin "2") (pinfunction "C_2") (pintype "passive"))
      (node (ref "OK2") (pin "2") (pinfunction "C_2") (pintype "passive"))
      (node (ref "OK3") (pin "2") (pinfunction "C_2") (pintype "passive"))
      (node (ref "OK4") (pin "2") (pinfunction "C_2") (pintype "passive"))
      (node (ref "OK5") (pin "2") (pinfunction "C_2") (pintype "passive"))
      (node (ref "OK6") (pin "2") (pinfunction "C_2") (pintype "passive"))
      (node (ref "OK7") (pin "2") (pinfunction "C_2") (pintype "passive"))
      (node (ref "OK8") (pin "2") (pinfunction "C_2") (pintype "passive"))
      (node (ref "R17") (pin "1") (pinfunction "1_1") (pintype "passive"))
      (node (ref "R18") (pin "1") (pinfunction "1_1") (pintype "passive"))
      (node (ref "R20") (pin "2") (pinfunction "2_2") (pintype "passive"))
      (node (ref "R21") (pin "1") (pinfunction "1_1") (pintype "passive"))
      (node (ref "R22") (pin "1") (pinfunction "1_1") (pintype "passive"))
      (node (ref "R23") (pin "1") (pinfunction "1_1") (pintype "passive"))
      (node (ref "R24") (pin "1") (pinfunction "1_1") (pintype "passive"))
      (node (ref "STM_D_CAPS1") (pin "2") (pinfunction "2_2") (pintype "passive"))
      (node (ref "STM_UART") (pin "4") (pinfunction "4_4") (pintype "passive"))
      (node (ref "SW1") (pin "P$2") (pinfunction "P$2_P$2") (pintype "passive"))
      (node (ref "U$1") (pin "14") (pinfunction "GND_14") (pintype "bidirectional"))
      (node (ref "U$1") (pin "32") (pinfunction "GND_32") (pintype "bidirectional"))
      (node (ref "U$1") (pin "38") (pinfunction "GND_38") (pintype "bidirectional"))
      (node (ref "U$2") (pin "P$19") (pinfunction "GND2_P$19") (pintype "bidirectional"))
      (node (ref "U$2") (pin "P$21") (pinfunction "GND1_P$21") (pintype "power_in"))
      (node (ref "U$2") (pin "P$22") (pinfunction "GND_P$22") (pintype "bidirectional"))
      (node (ref "U1") (pin "22") (pinfunction "GND_22") (pintype "bidirectional"))
      (node (ref "U1") (pin "8") (pinfunction "GND_8") (pintype "bidirectional"))
      (node (ref "X_CONN") (pin "4") (pinfunction "4_4") (pintype "passive"))
      (node (ref "Y1_CONN") (pin "4") (pinfunction "4_4") (pintype "passive"))
      (node (ref "Y2_CONN") (pin "4") (pinfunction "4_4") (pintype "passive"))
    )
    (net (code "54") (name "IO13") (class "Default")
      (node (ref "J4") (pin "15") (pinfunction "15_15") (pintype "passive"))
      (node (ref "U$1") (pin "15") (pinfunction "IO13_15") (pintype "bidirectional"))
    )
    (net (code "55") (name "IO15") (class "Default")
      (node (ref "J3") (pin "16") (pinfunction "16_16") (pintype "passive"))
      (node (ref "U$1") (pin "23") (pinfunction "IO15_23") (pintype "bidirectional"))
    )
    (net (code "56") (name "IO18") (class "Default")
      (node (ref "J3") (pin "9") (pinfunction "9_9") (pintype "passive"))
      (node (ref "U$1") (pin "30") (pinfunction "IO18_30") (pintype "bidirectional"))
    )
    (net (code "57") (name "IO19") (class "Default")
      (node (ref "J3") (pin "8") (pinfunction "8_8") (pintype "passive"))
      (node (ref "U$1") (pin "31") (pinfunction "IO19_31") (pintype "bidirectional"))
    )
    (net (code "58") (name "IO21") (class "Default")
      (node (ref "J3") (pin "6") (pinfunction "6_6") (pintype "passive"))
      (node (ref "U$1") (pin "33") (pinfunction "IO21_33") (pintype "bidirectional"))
    )
    (net (code "59") (name "IO34") (class "Default")
      (node (ref "J4") (pin "5") (pinfunction "5_5") (pintype "passive"))
      (node (ref "U$1") (pin "5") (pinfunction "IO34_5") (pintype "bidirectional"))
    )
    (net (code "60") (name "IO35") (class "Default")
      (node (ref "J4") (pin "6") (pinfunction "6_6") (pintype "passive"))
      (node (ref "U$1") (pin "6") (pinfunction "IO35_6") (pintype "bidirectional"))
    )
    (net (code "61") (name "LIMIT_SW1") (class "Default")
      (node (ref "J4") (pin "13") (pinfunction "13_13") (pintype "passive"))
      (node (ref "JP1") (pin "1") (pinfunction "1_1") (pintype "passive"))
      (node (ref "U$1") (pin "13") (pinfunction "IO12_13") (pintype "bidirectional"))
    )
    (net (code "62") (name "LIMIT_SW2") (class "Default")
      (node (ref "J4") (pin "12") (pinfunction "12_12") (pintype "passive"))
      (node (ref "JP2") (pin "1") (pinfunction "1_1") (pintype "passive"))
      (node (ref "U$1") (pin "12") (pinfunction "IO14_12") (pintype "bidirectional"))
    )
    (net (code "63") (name "LIMIT_SW3") (class "Default")
      (node (ref "J4") (pin "11") (pinfunction "11_11") (pintype "passive"))
      (node (ref "JP3") (pin "1") (pinfunction "1_1") (pintype "passive"))
      (node (ref "U$1") (pin "11") (pinfunction "IO27_11") (pintype "bidirectional"))
    )
    (net (code "64") (name "LIMIT_SW4") (class "Default")
      (node (ref "J4") (pin "10") (pinfunction "10_10") (pintype "passive"))
      (node (ref "JP4") (pin "1") (pinfunction "1_1") (pintype "passive"))
      (node (ref "U$1") (pin "10") (pinfunction "IO26_10") (pintype "bidirectional"))
    )
    (net (code "65") (name "LIMIT_SW5") (class "Default")
      (node (ref "J4") (pin "9") (pinfunction "9_9") (pintype "passive"))
      (node (ref "JP5") (pin "1") (pinfunction "1_1") (pintype "passive"))
      (node (ref "U$1") (pin "9") (pinfunction "IO25_9") (pintype "bidirectional"))
    )
    (net (code "66") (name "LIMIT_SW6") (class "Default")
      (node (ref "J4") (pin "8") (pinfunction "8_8") (pintype "passive"))
      (node (ref "JP6") (pin "1") (pinfunction "1_1") (pintype "passive"))
      (node (ref "U$1") (pin "8") (pinfunction "IO33_8") (pintype "bidirectional"))
    )
    (net (code "67") (name "LIMIT_SW7") (class "Default")
      (node (ref "J4") (pin "7") (pinfunction "7_7") (pintype "passive"))
      (node (ref "JP7") (pin "1") (pinfunction "1_1") (pintype "passive"))
      (node (ref "U$1") (pin "7") (pinfunction "IO32_7") (pintype "bidirectional"))
    )
    (net (code "68") (name "LIMIT_SWJ1") (class "Default")
      (node (ref "JP1") (pin "2") (pinfunction "2_2") (pintype "passive"))
      (node (ref "LIMIT_SW_CONN") (pin "1") (pinfunction "1_1") (pintype "passive"))
    )
    (net (code "69") (name "LIMIT_SWJ2") (class "Default")
      (node (ref "JP2") (pin "2") (pinfunction "2_2") (pintype "passive"))
      (node (ref "LIMIT_SW_CONN") (pin "2") (pinfunction "2_2") (pintype "passive"))
    )
    (net (code "70") (name "LIMIT_SWJ3") (class "Default")
      (node (ref "JP3") (pin "2") (pinfunction "2_2") (pintype "passive"))
      (node (ref "LIMIT_SW_CONN") (pin "3") (pinfunction "3_3") (pintype "passive"))
    )
    (net (code "71") (name "LIMIT_SWJ4") (class "Default")
      (node (ref "JP4") (pin "2") (pinfunction "2_2") (pintype "passive"))
      (node (ref "LIMIT_SW_CONN") (pin "4") (pinfunction "4_4") (pintype "passive"))
    )
    (net (code "72") (name "LIMIT_SWJ5") (class "Default")
      (node (ref "JP5") (pin "2") (pinfunction "2_2") (pintype "passive"))
      (node (ref "LIMIT_SW_CONN") (pin "5") (pinfunction "5_5") (pintype "passive"))
    )
    (net (code "73") (name "LIMIT_SWJ6") (class "Default")
      (node (ref "JP6") (pin "2") (pinfunction "2_2") (pintype "passive"))
      (node (ref "LIMIT_SW_CONN") (pin "6") (pinfunction "6_6") (pintype "passive"))
    )
    (net (code "74") (name "LIMIT_SWJ7") (class "Default")
      (node (ref "JP7") (pin "2") (pinfunction "2_2") (pintype "passive"))
      (node (ref "LIMIT_SW_CONN") (pin "7") (pinfunction "7_7") (pintype "passive"))
    )
    (net (code "75") (name "Net-(AT_LED-PadA)") (class "Default")
      (node (ref "AT_LED") (pin "A") (pinfunction "A_A") (pintype "passive"))
      (node (ref "R8") (pin "2") (pinfunction "2_2") (pintype "passive"))
    )
    (net (code "76") (name "Net-(JP16-Pad2)") (class "Default")
      (node (ref "JP16") (pin "2") (pinfunction "2_2") (pintype "passive"))
      (node (ref "R4") (pin "1") (pinfunction "1_1") (pintype "passive"))
    )
    (net (code "77") (name "Net-(JP17-Pad2)") (class "Default")
      (node (ref "JP17") (pin "2") (pinfunction "2_2") (pintype "passive"))
      (node (ref "R1") (pin "1") (pinfunction "1_1") (pintype "passive"))
    )
    (net (code "78") (name "Net-(JP18-Pad2)") (class "Default")
      (node (ref "JP18") (pin "2") (pinfunction "2_2") (pintype "passive"))
      (node (ref "R2") (pin "1") (pinfunction "1_1") (pintype "passive"))
    )
    (net (code "79") (name "Net-(JP19-Pad2)") (class "Default")
      (node (ref "JP19") (pin "2") (pinfunction "2_2") (pintype "passive"))
      (node (ref "R3") (pin "1") (pinfunction "1_1") (pintype "passive"))
    )
    (net (code "80") (name "Net-(JP20-Pad2)") (class "Default")
      (node (ref "JP20") (pin "2") (pinfunction "2_2") (pintype "passive"))
      (node (ref "R5") (pin "1") (pinfunction "1_1") (pintype "passive"))
    )
    (net (code "81") (name "Net-(JP21-Pad2)") (class "Default")
      (node (ref "JP21") (pin "2") (pinfunction "2_2") (pintype "passive"))
      (node (ref "R6") (pin "1") (pinfunction "1_1") (pintype "passive"))
    )
    (net (code "82") (name "Net-(JP23-Pad1)") (class "Default")
      (node (ref "JP23") (pin "1") (pinfunction "1_1") (pintype "passive"))
      (node (ref "R19") (pin "1") (pinfunction "1_1") (pintype "passive"))
    )
    (net (code "83") (name "Net-(OK1-A)") (class "Default")
      (node (ref "OK1") (pin "1") (pinfunction "A_1") (pintype "passive"))
      (node (ref "R11") (pin "2") (pinfunction "2_2") (pintype "passive"))
    )
    (net (code "84") (name "Net-(OK2-A)") (class "Default")
      (node (ref "OK2") (pin "1") (pinfunction "A_1") (pintype "passive"))
      (node (ref "R14") (pin "2") (pinfunction "2_2") (pintype "passive"))
    )
    (net (code "85") (name "Net-(OK3-A)") (class "Default")
      (node (ref "OK3") (pin "1") (pinfunction "A_1") (pintype "passive"))
      (node (ref "R10") (pin "2") (pinfunction "2_2") (pintype "passive"))
    )
    (net (code "86") (name "Net-(OK4-A)") (class "Default")
      (node (ref "OK4") (pin "1") (pinfunction "A_1") (pintype "passive"))
      (node (ref "R9") (pin "2") (pinfunction "2_2") (pintype "passive"))
    )
    (net (code "87") (name "Net-(OK5-A)") (class "Default")
      (node (ref "OK5") (pin "1") (pinfunction "A_1") (pintype "passive"))
      (node (ref "R12") (pin "2") (pinfunction "2_2") (pintype "passive"))
    )
    (net (code "88") (name "Net-(OK6-A)") (class "Default")
      (node (ref "OK6") (pin "1") (pinfunction "A_1") (pintype "passive"))
      (node (ref "R13") (pin "2") (pinfunction "2_2") (pintype "passive"))
    )
    (net (code "89") (name "Net-(OK7-A)") (class "Default")
      (node (ref "OK7") (pin "1") (pinfunction "A_1") (pintype "passive"))
      (node (ref "R15") (pin "2") (pinfunction "2_2") (pintype "passive"))
    )
    (net (code "90") (name "Net-(OK8-A)") (class "Default")
      (node (ref "OK8") (pin "1") (pinfunction "A_1") (pintype "passive"))
      (node (ref "R16") (pin "2") (pinfunction "2_2") (pintype "passive"))
    )
    (net (code "91") (name "Net-(U1-AREF)") (class "Default")
      (node (ref "C7") (pin "1") (pinfunction "1_1") (pintype "passive"))
      (node (ref "U1") (pin "21") (pinfunction "AREF_21") (pintype "bidirectional"))
    )
    (net (code "92") (name "Net-(U1-PB6(XTAL1{slash}TOSC1))") (class "Default")
      (node (ref "C14") (pin "2") (pinfunction "2_2") (pintype "passive"))
      (node (ref "CRYST") (pin "2") (pinfunction "2_2") (pintype "passive"))
      (node (ref "U1") (pin "9") (pinfunction "PB6(XTAL1/TOSC1)_9") (pintype "bidirectional"))
    )
    (net (code "93") (name "Net-(U1-PB7(XTAL2{slash}TOSC2))") (class "Default")
      (node (ref "C13") (pin "2") (pinfunction "2_2") (pintype "passive"))
      (node (ref "CRYST") (pin "1") (pinfunction "1_1") (pintype "passive"))
      (node (ref "U1") (pin "10") (pinfunction "PB7(XTAL2/TOSC2)_10") (pintype "bidirectional"))
    )
    (net (code "94") (name "SD0") (class "Default")
      (node (ref "J3") (pin "18") (pinfunction "18_18") (pintype "passive"))
      (node (ref "U$1") (pin "21") (pinfunction "SD0_21") (pintype "bidirectional"))
    )
    (net (code "95") (name "SD1") (class "Default")
      (node (ref "J3") (pin "17") (pinfunction "17_17") (pintype "passive"))
      (node (ref "U$1") (pin "22") (pinfunction "SD1_22") (pintype "bidirectional"))
    )
    (net (code "96") (name "SD2") (class "Default")
      (node (ref "J4") (pin "16") (pinfunction "16_16") (pintype "passive"))
      (node (ref "U$1") (pin "16") (pinfunction "SD2_16") (pintype "bidirectional"))
    )
    (net (code "97") (name "SD3") (class "Default")
      (node (ref "J4") (pin "17") (pinfunction "17_17") (pintype "passive"))
      (node (ref "U$1") (pin "17") (pinfunction "SD3_17") (pintype "bidirectional"))
    )
    (net (code "98") (name "SMP_GND") (class "Default")
      (node (ref "MOTOR_X") (pin "2") (pinfunction "2_2") (pintype "passive"))
      (node (ref "MOTOR_X") (pin "3") (pinfunction "3_3") (pintype "passive"))
      (node (ref "MOTOR_Y1") (pin "2") (pinfunction "2_2") (pintype "passive"))
      (node (ref "MOTOR_Y1") (pin "3") (pinfunction "3_3") (pintype "passive"))
      (node (ref "MOTOR_Y2") (pin "2") (pinfunction "2_2") (pintype "passive"))
      (node (ref "MOTOR_Y2") (pin "3") (pinfunction "3_3") (pintype "passive"))
      (node (ref "MOTOR_Z") (pin "2") (pinfunction "2_2") (pintype "passive"))
      (node (ref "MOTOR_Z") (pin "3") (pinfunction "3_3") (pintype "passive"))
    )
    (net (code "99") (name "STEP_X") (class "Default")
      (node (ref "R9") (pin "1") (pinfunction "1_1") (pintype "passive"))
      (node (ref "U1") (pin "4") (pinfunction "PD2(INT0)_4") (pintype "bidirectional"))
    )
    (net (code "100") (name "STEP_XO") (class "Default")
      (node (ref "MOTOR_X") (pin "1") (pinfunction "1_1") (pintype "passive"))
      (node (ref "OK4") (pin "3") (pinfunction "EMIT_3") (pintype "passive"))
    )
    (net (code "101") (name "STEP_Y") (class "Default")
      (node (ref "R10") (pin "1") (pinfunction "1_1") (pintype "passive"))
      (node (ref "R15") (pin "1") (pinfunction "1_1") (pintype "passive"))
      (node (ref "U1") (pin "5") (pinfunction "PD3(INT1)_5") (pintype "bidirectional"))
    )
    (net (code "102") (name "STEP_Y1O") (class "Default")
      (node (ref "MOTOR_Y1") (pin "1") (pinfunction "1_1") (pintype "passive"))
      (node (ref "OK3") (pin "3") (pinfunction "EMIT_3") (pintype "passive"))
    )
    (net (code "103") (name "STEP_Y2O") (class "Default")
      (node (ref "MOTOR_Y2") (pin "1") (pinfunction "1_1") (pintype "passive"))
      (node (ref "OK7") (pin "3") (pinfunction "EMIT_3") (pintype "passive"))
    )
    (net (code "104") (name "STEP_Z") (class "Default")
      (node (ref "R11") (pin "1") (pinfunction "1_1") (pintype "passive"))
      (node (ref "U1") (pin "6") (pinfunction "PD4(XCK/T0)_6") (pintype "bidirectional"))
    )
    (net (code "105") (name "STEP_ZO") (class "Default")
      (node (ref "MOTOR_Z") (pin "1") (pinfunction "1_1") (pintype "passive"))
      (node (ref "OK1") (pin "3") (pinfunction "EMIT_3") (pintype "passive"))
    )
    (net (code "106") (name "STM_5V") (class "Default")
      (node (ref "STM_UART") (pin "3") (pinfunction "3_3") (pintype "passive"))
      (node (ref "U$2") (pin "P$18") (pinfunction "5V_P$18") (pintype "bidirectional"))
    )
    (net (code "107") (name "STM_RX") (class "Default")
      (node (ref "STM_UART") (pin "1") (pinfunction "1_1") (pintype "passive"))
      (node (ref "U$2") (pin "P$6") (pinfunction "PA9_P$6") (pintype "bidirectional"))
    )
    (net (code "108") (name "STM_TX") (class "Default")
      (node (ref "STM_UART") (pin "2") (pinfunction "2_2") (pintype "passive"))
      (node (ref "U$2") (pin "P$7") (pinfunction "PA10_P$7") (pintype "bidirectional"))
    )
    (net (code "109") (name "STM_VBAT") (class "Default")
      (node (ref "C11") (pin "1") (pinfunction "1_1") (pintype "passive"))
      (node (ref "C6") (pin "1") (pinfunction "1_1") (pintype "passive"))
      (node (ref "IC2") (pin "3") (pinfunction "VO_3") (pintype "passive"))
      (node (ref "STM_D_CAPS1") (pin "1") (pinfunction "1_1") (pintype "passive"))
      (node (ref "U$2") (pin "P$40") (pinfunction "VBAT_P$40") (pintype "bidirectional"))
      (node (ref "X_CONN") (pin "3") (pinfunction "3_3") (pintype "passive"))
      (node (ref "Y1_CONN") (pin "3") (pinfunction "3_3") (pintype "passive"))
      (node (ref "Y2_CONN") (pin "3") (pinfunction "3_3") (pintype "passive"))
    )
    (net (code "110") (name "SVN") (class "Default")
      (node (ref "J4") (pin "4") (pinfunction "4_4") (pintype "passive"))
      (node (ref "U$1") (pin "4") (pinfunction "SVN_4") (pintype "bidirectional"))
    )
    (net (code "111") (name "SVP") (class "Default")
      (node (ref "J4") (pin "3") (pinfunction "3_3") (pintype "passive"))
      (node (ref "U$1") (pin "3") (pinfunction "SVP_3") (pintype "bidirectional"))
    )
    (net (code "112") (name "unconnected-(S1-Pad1)") (class "Default")
      (node (ref "S1") (pin "1") (pinfunction "1_1") (pintype "passive"))
    )
    (net (code "113") (name "unconnected-(S1-Pad3)") (class "Default")
      (node (ref "S1") (pin "3") (pinfunction "3_3") (pintype "passive"))
    )
    (net (code "114") (name "unconnected-(U$2-3.3V-PadP$23)") (class "Default")
      (node (ref "U$2") (pin "P$23") (pinfunction "3.3V_P$23") (pintype "bidirectional"))
    )
    (net (code "115") (name "unconnected-(U$2-3.3V1-PadP$20)") (class "Default")
      (node (ref "U$2") (pin "P$20") (pinfunction "3.3V1_P$20") (pintype "bidirectional"))
    )
    (net (code "116") (name "unconnected-(U$2-PA0-PadP$36)") (class "Default")
      (node (ref "U$2") (pin "P$36") (pinfunction "PA0_P$36") (pintype "bidirectional"))
    )
    (net (code "117") (name "unconnected-(U$2-PA1-PadP$35)") (class "Default")
      (node (ref "U$2") (pin "P$35") (pinfunction "PA1_P$35") (pintype "bidirectional"))
    )
    (net (code "118") (name "unconnected-(U$2-PA2-PadP$34)") (class "Default")
      (node (ref "U$2") (pin "P$34") (pinfunction "PA2_P$34") (pintype "bidirectional"))
    )
    (net (code "119") (name "unconnected-(U$2-PA3-PadP$33)") (class "Default")
      (node (ref "U$2") (pin "P$33") (pinfunction "PA3_P$33") (pintype "bidirectional"))
    )
    (net (code "120") (name "unconnected-(U$2-PA4-PadP$32)") (class "Default")
      (node (ref "U$2") (pin "P$32") (pinfunction "PA4_P$32") (pintype "bidirectional"))
    )
    (net (code "121") (name "unconnected-(U$2-PA5-PadP$31)") (class "Default")
      (node (ref "U$2") (pin "P$31") (pinfunction "PA5_P$31") (pintype "bidirectional"))
    )
    (net (code "122") (name "unconnected-(U$2-PA6-PadP$30)") (class "Default")
      (node (ref "U$2") (pin "P$30") (pinfunction "PA6_P$30") (pintype "bidirectional"))
    )
    (net (code "123") (name "unconnected-(U$2-PA7-PadP$29)") (class "Default")
      (node (ref "U$2") (pin "P$29") (pinfunction "PA7_P$29") (pintype "bidirectional"))
    )
    (net (code "124") (name "unconnected-(U$2-PA8-PadP$5)") (class "Default")
      (node (ref "U$2") (pin "P$5") (pinfunction "PA8_P$5") (pintype "bidirectional"))
    )
    (net (code "125") (name "unconnected-(U$2-PA11-PadP$8)") (class "Default")
      (node (ref "U$2") (pin "P$8") (pinfunction "PA11_P$8") (pintype "bidirectional"))
    )
    (net (code "126") (name "unconnected-(U$2-PA12-PadP$9)") (class "Default")
      (node (ref "U$2") (pin "P$9") (pinfunction "PA12_P$9") (pintype "bidirectional"))
    )
    (net (code "127") (name "unconnected-(U$2-PA15-PadP$10)") (class "Default")
      (node (ref "U$2") (pin "P$10") (pinfunction "PA15_P$10") (pintype "bidirectional"))
    )
    (net (code "128") (name "unconnected-(U$2-PB0-PadP$28)") (class "Default")
      (node (ref "U$2") (pin "P$28") (pinfunction "PB0_P$28") (pintype "bidirectional"))
    )
    (net (code "129") (name "unconnected-(U$2-PB1-PadP$27)") (class "Default")
      (node (ref "U$2") (pin "P$27") (pinfunction "PB1_P$27") (pintype "bidirectional"))
    )
    (net (code "130") (name "unconnected-(U$2-PB3-PadP$11)") (class "Default")
      (node (ref "U$2") (pin "P$11") (pinfunction "PB3_P$11") (pintype "bidirectional"))
    )
    (net (code "131") (name "unconnected-(U$2-PB4-PadP$12)") (class "Default")
      (node (ref "U$2") (pin "P$12") (pinfunction "PB4_P$12") (pintype "bidirectional"))
    )
    (net (code "132") (name "unconnected-(U$2-PB10-PadP$26)") (class "Default")
      (node (ref "U$2") (pin "P$26") (pinfunction "PB10_P$26") (pintype "bidirectional"))
    )
    (net (code "133") (name "unconnected-(U$2-PB11-PadP$25)") (class "Default")
      (node (ref "U$2") (pin "P$25") (pinfunction "PB11_P$25") (pintype "bidirectional"))
    )
    (net (code "134") (name "unconnected-(U$2-PB14-PadP$3)") (class "Default")
      (node (ref "U$2") (pin "P$3") (pinfunction "PB14_P$3") (pintype "bidirectional"))
    )
    (net (code "135") (name "unconnected-(U$2-PC13-PadP$39)") (class "Default")
      (node (ref "U$2") (pin "P$39") (pinfunction "PC13_P$39") (pintype "bidirectional"))
    )
    (net (code "136") (name "unconnected-(U$2-PC14-PadP$38)") (class "Default")
      (node (ref "U$2") (pin "P$38") (pinfunction "PC14_P$38") (pintype "bidirectional"))
    )
    (net (code "137") (name "unconnected-(U$2-PC15-PadP$37)") (class "Default")
      (node (ref "U$2") (pin "P$37") (pinfunction "PC15_P$37") (pintype "bidirectional"))
    )
    (net (code "138") (name "unconnected-(U$2-RESET-PadP$24)") (class "Default")
      (node (ref "U$2") (pin "P$24") (pinfunction "RESET_P$24") (pintype "bidirectional"))
    )
    (net (code "139") (name "unconnected-(U1-PB0(ICP)-Pad14)") (class "Default")
      (node (ref "U1") (pin "14") (pinfunction "PB0(ICP)_14") (pintype "bidirectional"))
    )
    (net (code "140") (name "unconnected-(U1-PB1(OC1A)-Pad15)") (class "Default")
      (node (ref "U1") (pin "15") (pinfunction "PB1(OC1A)_15") (pintype "bidirectional"))
    )
    (net (code "141") (name "unconnected-(U1-PC0(ADC0)-Pad23)") (class "Default")
      (node (ref "U1") (pin "23") (pinfunction "PC0(ADC0)_23") (pintype "bidirectional"))
    )
    (net (code "142") (name "unconnected-(U1-PC1(ADC1)-Pad24)") (class "Default")
      (node (ref "U1") (pin "24") (pinfunction "PC1(ADC1)_24") (pintype "bidirectional"))
    )
    (net (code "143") (name "unconnected-(U1-PC2(ADC2)-Pad25)") (class "Default")
      (node (ref "U1") (pin "25") (pinfunction "PC2(ADC2)_25") (pintype "bidirectional"))
    )
    (net (code "144") (name "unconnected-(U1-PC3(ADC3)-Pad26)") (class "Default")
      (node (ref "U1") (pin "26") (pinfunction "PC3(ADC3)_26") (pintype "bidirectional"))
    )
    (net (code "145") (name "unconnected-(U1-PC4(ADC4{slash}SDA)-Pad27)") (class "Default")
      (node (ref "U1") (pin "27") (pinfunction "PC4(ADC4/SDA)_27") (pintype "bidirectional"))
    )
    (net (code "146") (name "unconnected-(U1-PC5(ADC5{slash}SCL)-Pad28)") (class "Default")
      (node (ref "U1") (pin "28") (pinfunction "PC5(ADC5/SCL)_28") (pintype "bidirectional"))
    )
  )
)
